# amp-LNA-TQP3M9037.net
KiCad netlist of a schematic drawn in EAGLE
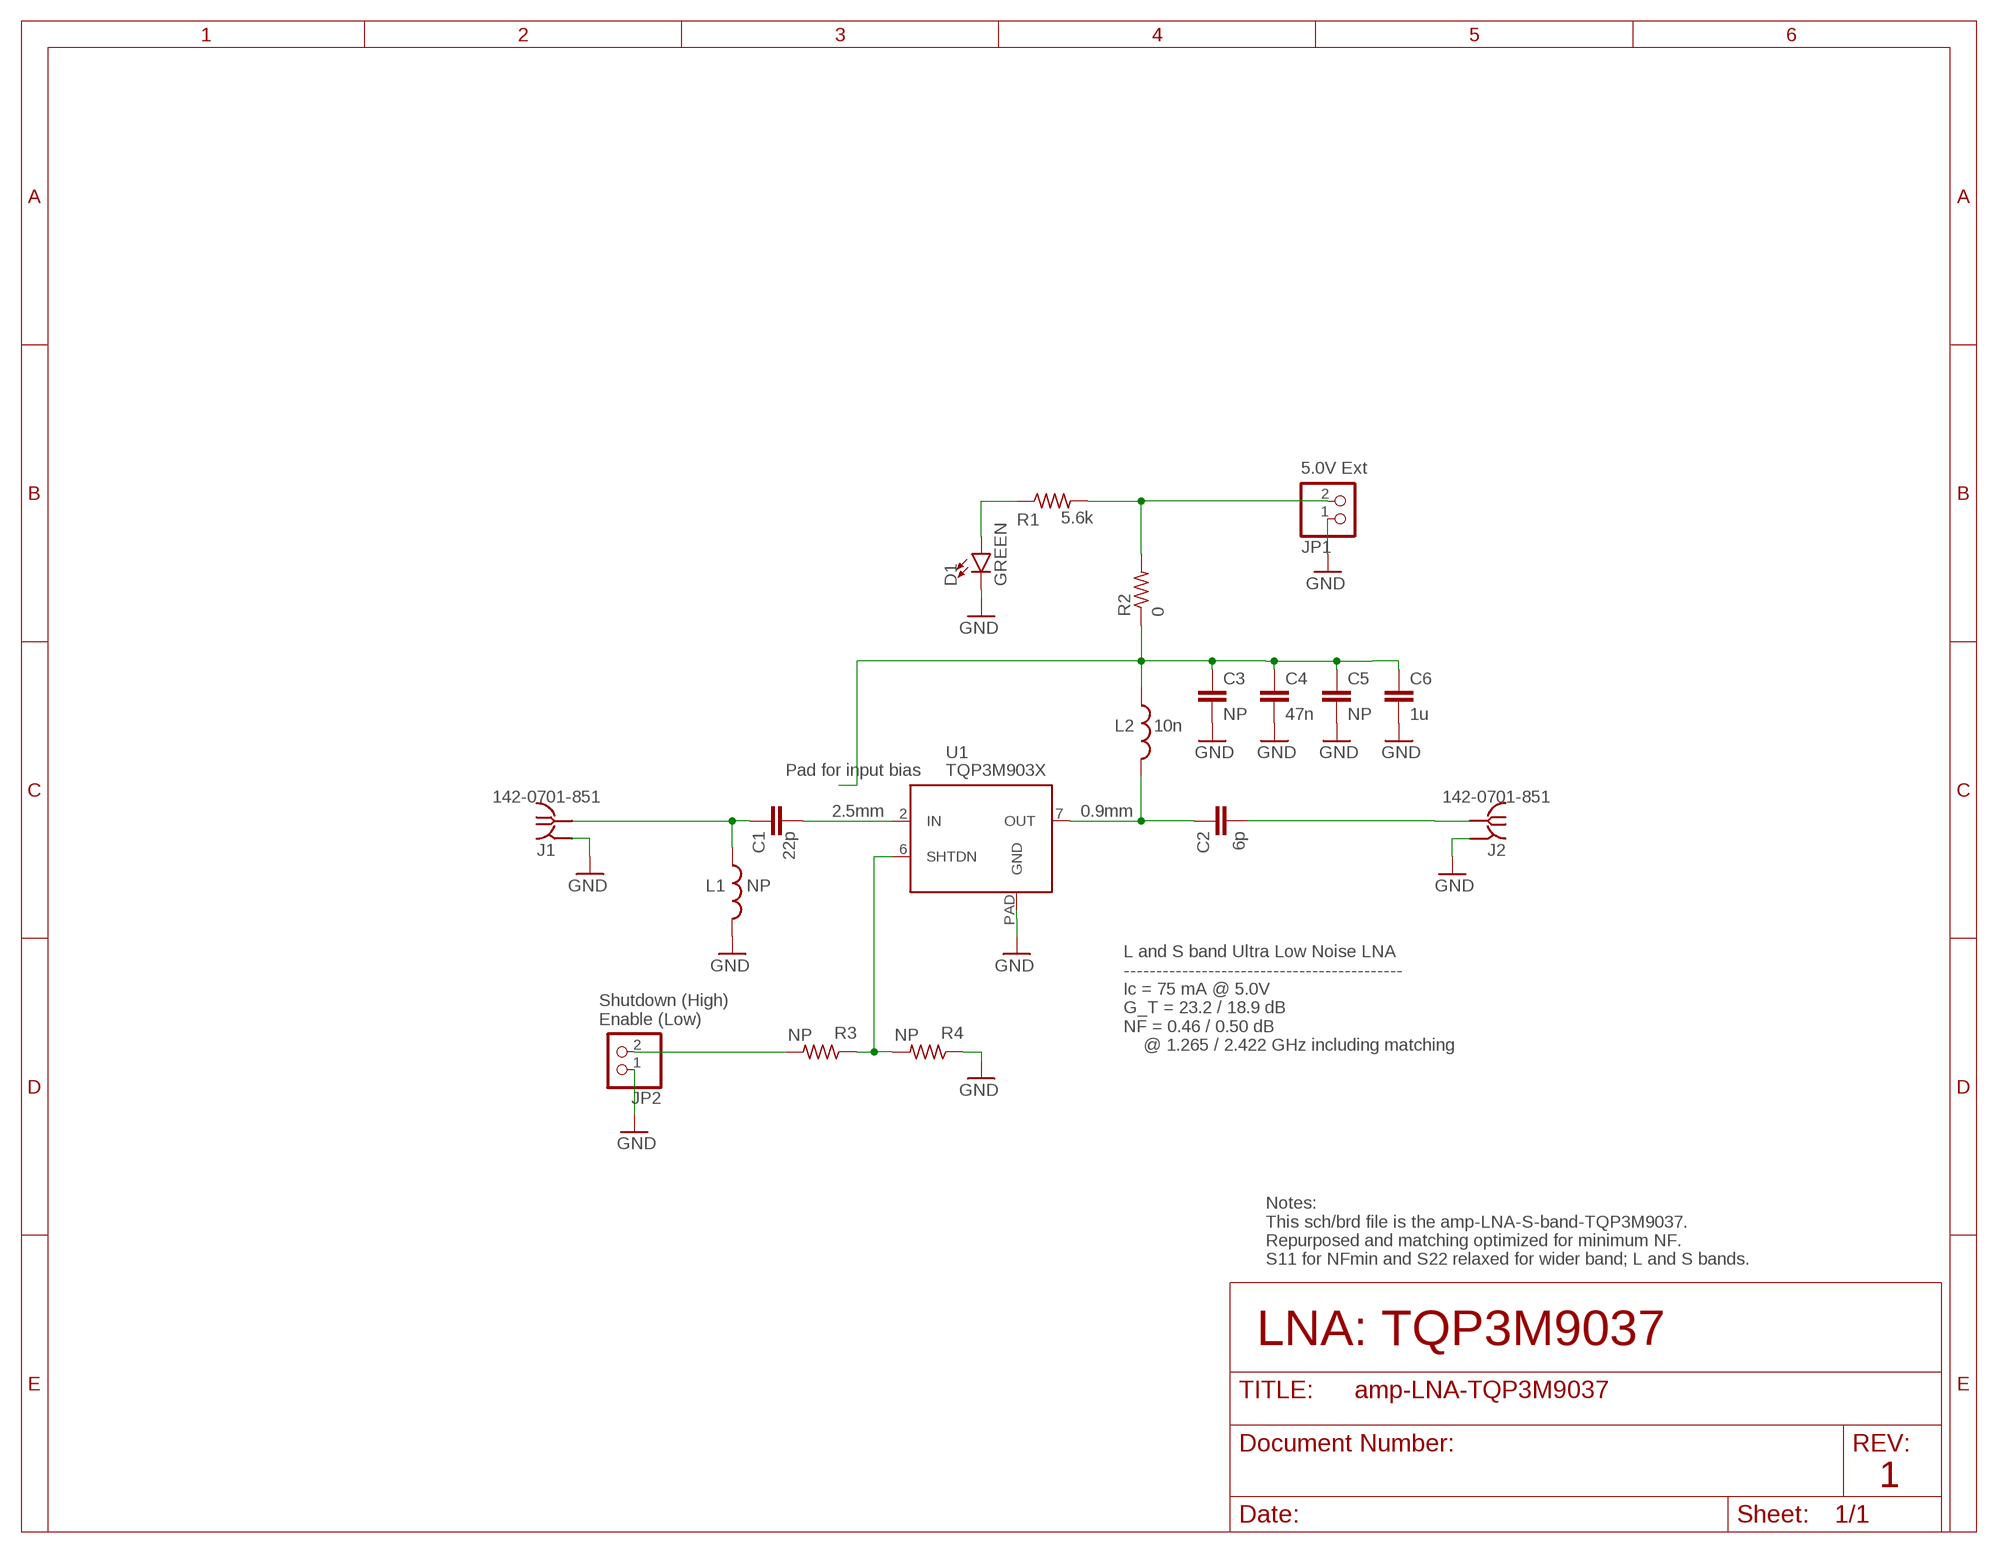
[diagram p0: schematic, sheet 1]

(export (version "E")
  (design (tool "Eeschema 10.0.6"))
  (components
    (comp (ref "C1")
      (value "22p")
      (footprint "eagle-import:.0402-C-NOSILK")
      (libsource (lib "eagle-import") (part "C-EU0402-C-NOSILK"))
    )
    (comp (ref "C2")
      (value "6p")
      (footprint "eagle-import:.0402-C-NOSILK")
      (libsource (lib "eagle-import") (part "C-EU0402-C-NOSILK"))
    )
    (comp (ref "C3")
      (value "NP")
      (footprint "eagle-import:.0603-B-NOSILK")
      (libsource (lib "eagle-import") (part "C-EU0603-B-NOSILK"))
    )
    (comp (ref "C4")
      (value "47n")
      (footprint "eagle-import:.0603-B-NOSILK")
      (libsource (lib "eagle-import") (part "C-EU0603-B-NOSILK"))
    )
    (comp (ref "C5")
      (value "NP")
      (footprint "eagle-import:.0603-B-NOSILK")
      (libsource (lib "eagle-import") (part "C-EU0603-B-NOSILK"))
    )
    (comp (ref "C6")
      (value "1u")
      (footprint "eagle-import:.0603-B-NOSILK")
      (libsource (lib "eagle-import") (part "C-EU0603-B-NOSILK"))
    )
    (comp (ref "D1")
      (value "GREEN")
      (footprint "eagle-import:LED-0603")
      (libsource (lib "eagle-import") (part "LED-GREEN0603"))
    )
    (comp (ref "J1")
      (value "142-0701-851")
      (footprint "eagle-import:142-0701-851")
      (libsource (lib "eagle-import") (part "142-0701-851"))
    )
    (comp (ref "J2")
      (value "142-0701-851")
      (footprint "eagle-import:142-0701-851")
      (libsource (lib "eagle-import") (part "142-0701-851"))
    )
    (comp (ref "JP1")
      (value "PINHD-1X2")
      (footprint "eagle-import:1X02")
      (libsource (lib "eagle-import") (part "PINHD-1X2"))
    )
    (comp (ref "JP2")
      (value "PINHD-1X2")
      (footprint "eagle-import:1X02")
      (libsource (lib "eagle-import") (part "PINHD-1X2"))
    )
    (comp (ref "L1")
      (value "NP")
      (footprint "eagle-import:.0402-C-NOSILK")
      (libsource (lib "eagle-import") (part "L-US0402-C-NOSILK"))
    )
    (comp (ref "L2")
      (value "10n")
      (footprint "eagle-import:.0603-C-NOSILK")
      (libsource (lib "eagle-import") (part "L-US0603-C-NOSILK"))
    )
    (comp (ref "R1")
      (value "5.6k")
      (footprint "eagle-import:.0603-B-NOSILK")
      (libsource (lib "eagle-import") (part "R-US_0603-B-NOSILK"))
    )
    (comp (ref "R2")
      (value "0")
      (footprint "eagle-import:.0603-B-NOSILK")
      (libsource (lib "eagle-import") (part "R-US_0603-B-NOSILK"))
    )
    (comp (ref "R3")
      (value "NP")
      (footprint "eagle-import:.0603-B-NOSILK")
      (libsource (lib "eagle-import") (part "R-US_0603-B-NOSILK"))
    )
    (comp (ref "R4")
      (value "NP")
      (footprint "eagle-import:.0603-B-NOSILK")
      (libsource (lib "eagle-import") (part "R-US_0603-B-NOSILK"))
    )
    (comp (ref "U1")
      (value "TQP3M903X")
      (footprint "eagle-import:DFN8-2X2-WITH-PAD")
      (libsource (lib "eagle-import") (part "TQP3M903X"))
    )
  )
  (nets
    (net (code "1") (name "GND") (class "Default")
      (node (ref "C3") (pin "2") (pinfunction "2_2") (pintype "passive"))
      (node (ref "C4") (pin "2") (pinfunction "2_2") (pintype "passive"))
      (node (ref "C5") (pin "2") (pinfunction "2_2") (pintype "passive"))
      (node (ref "C6") (pin "2") (pinfunction "2_2") (pintype "passive"))
      (node (ref "D1") (pin "C") (pinfunction "C_C") (pintype "passive"))
      (node (ref "J1") (pin "GND1") (pinfunction "GND_GND1") (pintype "bidirectional"))
      (node (ref "J1") (pin "GND2") (pinfunction "GND_GND2") (pintype "bidirectional"))
      (node (ref "J1") (pin "GND3") (pinfunction "GND_GND3") (pintype "bidirectional"))
      (node (ref "J1") (pin "GND4") (pinfunction "GND_GND4") (pintype "bidirectional"))
      (node (ref "J2") (pin "GND1") (pinfunction "GND_GND1") (pintype "bidirectional"))
      (node (ref "J2") (pin "GND2") (pinfunction "GND_GND2") (pintype "bidirectional"))
      (node (ref "J2") (pin "GND3") (pinfunction "GND_GND3") (pintype "bidirectional"))
      (node (ref "J2") (pin "GND4") (pinfunction "GND_GND4") (pintype "bidirectional"))
      (node (ref "JP1") (pin "1") (pinfunction "1_1") (pintype "passive"))
      (node (ref "JP2") (pin "1") (pinfunction "1_1") (pintype "passive"))
      (node (ref "L1") (pin "2") (pinfunction "2_2") (pintype "passive"))
      (node (ref "R4") (pin "1") (pinfunction "1_1") (pintype "passive"))
      (node (ref "U1") (pin "PAD") (pinfunction "GND_PAD") (pintype "power_in"))
    )
    (net (code "2") (name "Net-(C3-Pad1)") (class "Default")
      (node (ref "C3") (pin "1") (pinfunction "1_1") (pintype "passive"))
      (node (ref "C4") (pin "1") (pinfunction "1_1") (pintype "passive"))
      (node (ref "C5") (pin "1") (pinfunction "1_1") (pintype "passive"))
      (node (ref "C6") (pin "1") (pinfunction "1_1") (pintype "passive"))
      (node (ref "L2") (pin "1") (pinfunction "1_1") (pintype "passive"))
      (node (ref "R2") (pin "1") (pinfunction "1_1") (pintype "passive"))
    )
    (net (code "3") (name "Net-(D1-PadA)") (class "Default")
      (node (ref "D1") (pin "A") (pinfunction "A_A") (pintype "passive"))
      (node (ref "R1") (pin "1") (pinfunction "1_1") (pintype "passive"))
    )
    (net (code "4") (name "Net-(J1-RF)") (class "Default")
      (node (ref "C1") (pin "1") (pinfunction "1_1") (pintype "passive"))
      (node (ref "J1") (pin "RF1") (pinfunction "RF_RF1") (pintype "bidirectional"))
      (node (ref "L1") (pin "1") (pinfunction "1_1") (pintype "passive"))
    )
    (net (code "5") (name "Net-(J2-RF)") (class "Default")
      (node (ref "C2") (pin "2") (pinfunction "2_2") (pintype "passive"))
      (node (ref "J2") (pin "RF1") (pinfunction "RF_RF1") (pintype "bidirectional"))
    )
    (net (code "6") (name "Net-(JP1-Pad2)") (class "Default")
      (node (ref "JP1") (pin "2") (pinfunction "2_2") (pintype "passive"))
      (node (ref "R1") (pin "2") (pinfunction "2_2") (pintype "passive"))
      (node (ref "R2") (pin "2") (pinfunction "2_2") (pintype "passive"))
    )
    (net (code "7") (name "Net-(JP2-Pad2)") (class "Default")
      (node (ref "JP2") (pin "2") (pinfunction "2_2") (pintype "passive"))
      (node (ref "R3") (pin "2") (pinfunction "2_2") (pintype "passive"))
    )
    (net (code "8") (name "Net-(U1-IN)") (class "Default")
      (node (ref "C1") (pin "2") (pinfunction "2_2") (pintype "passive"))
      (node (ref "U1") (pin "2") (pinfunction "IN_2") (pintype "input"))
    )
    (net (code "9") (name "Net-(U1-OUT)") (class "Default")
      (node (ref "C2") (pin "1") (pinfunction "1_1") (pintype "passive"))
      (node (ref "L2") (pin "2") (pinfunction "2_2") (pintype "passive"))
      (node (ref "U1") (pin "7") (pinfunction "OUT_7") (pintype "output"))
    )
    (net (code "10") (name "Net-(U1-SHTDN)") (class "Default")
      (node (ref "R3") (pin "1") (pinfunction "1_1") (pintype "passive"))
      (node (ref "R4") (pin "2") (pinfunction "2_2") (pintype "passive"))
      (node (ref "U1") (pin "6") (pinfunction "SHTDN_6") (pintype "input"))
    )
  )
)
